# ElectronicThermometerCPO_v7.net
KiCad netlist of a schematic drawn in EAGLE
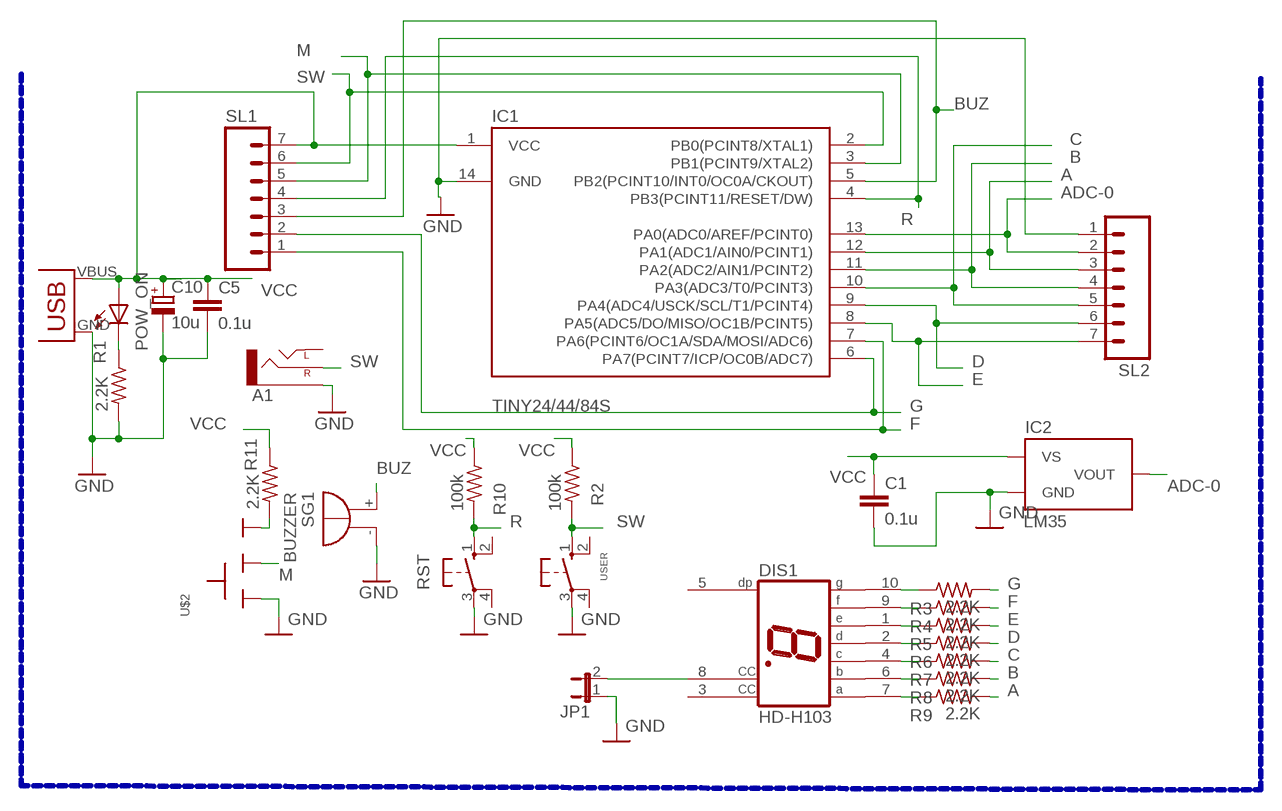
[diagram p0: schematic, sheet 1]

(export (version "E")
  (design (tool "Eeschema 10.0.6"))
  (components
    (comp (ref "A1")
      (value "AUDIO-JACKPTH")
      (footprint "eagle-import:AUDIO-JACK")
      (libsource (lib "eagle-import") (part "AUDIO-JACKPTH"))
    )
    (comp (ref "C1")
      (value "0.1u")
      (footprint "eagle-import:C0805")
      (libsource (lib "eagle-import") (part "C-EUC0805"))
    )
    (comp (ref "C5")
      (value "0.1u")
      (footprint "eagle-import:C0805")
      (libsource (lib "eagle-import") (part "C-EUC0805"))
    )
    (comp (ref "C10")
      (value "10u")
      (footprint "eagle-import:B_3528-21R")
      (libsource (lib "eagle-import") (part "CPOL-EUB/3528-21R"))
    )
    (comp (ref "DIS1")
      (value "HD-H103")
      (footprint "eagle-import:HDSP-M")
      (libsource (lib "eagle-import") (part "HD-H103"))
    )
    (comp (ref "IC1")
      (value "TINY24/44/84S")
      (footprint "eagle-import:SOIC14")
      (libsource (lib "eagle-import") (part "TINY24/44/84S"))
    )
    (comp (ref "IC2")
      (value "LM35")
      (footprint "eagle-import:TO92")
      (libsource (lib "eagle-import") (part "LM35"))
    )
    (comp (ref "JP1")
      (value "JP1E")
      (footprint "eagle-import:JP1")
      (libsource (lib "eagle-import") (part "JP1E"))
    )
    (comp (ref "POW_ON")
      (value "LED3MM")
      (footprint "eagle-import:LED3MM")
      (libsource (lib "eagle-import") (part "LED3MM"))
    )
    (comp (ref "R1")
      (value "2.2K")
      (footprint "eagle-import:0207_10")
      (libsource (lib "eagle-import") (part "R-US_0207/10"))
    )
    (comp (ref "R2")
      (value "100k")
      (footprint "eagle-import:0207_10")
      (libsource (lib "eagle-import") (part "R-US_0207/10"))
    )
    (comp (ref "R3")
      (value "2.2K")
      (footprint "eagle-import:0207_10")
      (libsource (lib "eagle-import") (part "R-US_0207/10"))
    )
    (comp (ref "R4")
      (value "2.2K")
      (footprint "eagle-import:0207_10")
      (libsource (lib "eagle-import") (part "R-US_0207/10"))
    )
    (comp (ref "R5")
      (value "2.2K")
      (footprint "eagle-import:0207_10")
      (libsource (lib "eagle-import") (part "R-US_0207/10"))
    )
    (comp (ref "R6")
      (value "2.2K")
      (footprint "eagle-import:0207_10")
      (libsource (lib "eagle-import") (part "R-US_0207/10"))
    )
    (comp (ref "R7")
      (value "2.2K")
      (footprint "eagle-import:0207_10")
      (libsource (lib "eagle-import") (part "R-US_0207/10"))
    )
    (comp (ref "R8")
      (value "2.2K")
      (footprint "eagle-import:0207_10")
      (libsource (lib "eagle-import") (part "R-US_0207/10"))
    )
    (comp (ref "R9")
      (value "2.2K")
      (footprint "eagle-import:0207_10")
      (libsource (lib "eagle-import") (part "R-US_0207/10"))
    )
    (comp (ref "R10")
      (value "100k")
      (footprint "eagle-import:0207_10")
      (libsource (lib "eagle-import") (part "R-US_0207/10"))
    )
    (comp (ref "R11")
      (value "2.2K")
      (footprint "eagle-import:0207_10")
      (libsource (lib "eagle-import") (part "R-US_0207/10"))
    )
    (comp (ref "RST")
      (value "10-XX")
      (footprint "eagle-import:B3F-10XX")
      (fields (field (name "MPN") "B3F-1000"))
      (libsource (lib "eagle-import") (part "10-XX"))
    )
    (comp (ref "SG1")
      (value "BUZZER")
      (footprint "eagle-import:F_TMB")
      (libsource (lib "eagle-import") (part "BUZZER"))
    )
    (comp (ref "SL1")
      (value "M07")
      (footprint "eagle-import:07P")
      (libsource (lib "eagle-import") (part "M07"))
    )
    (comp (ref "SL2")
      (value "M07")
      (footprint "eagle-import:07P")
      (libsource (lib "eagle-import") (part "M07"))
    )
    (comp (ref "U$1")
      (value "USB(POWER)")
      (footprint "eagle-import:USB(POWER)")
      (libsource (lib "eagle-import") (part "USB(POWER)"))
    )
    (comp (ref "U$2")
      (value "SLIDESWITCH-BIG")
      (footprint "eagle-import:BIGSWITCH")
      (libsource (lib "eagle-import") (part "SLIDESWITCH-BIG"))
    )
    (comp (ref "USER")
      (value "40-XX")
      (footprint "eagle-import:B3F-40XX")
      (fields (field (name "MF") "OMRON COMPONENTS USA") (field (name "MPN") "B3F-4000"))
      (libsource (lib "eagle-import") (part "40-XX"))
    )
  )
  (nets
    (net (code "1") (name "/A") (class "Default")
      (node (ref "IC1") (pin "12") (pinfunction "PA1(ADC1/AIN0/PCINT1)_12") (pintype "bidirectional"))
      (node (ref "R9") (pin "2") (pinfunction "2_2") (pintype "passive"))
      (node (ref "SL2") (pin "3") (pinfunction "3_3") (pintype "passive"))
    )
    (net (code "2") (name "/ADC-0") (class "Default")
      (node (ref "IC1") (pin "13") (pinfunction "PA0(ADC0/AREF/PCINT0)_13") (pintype "bidirectional"))
      (node (ref "IC2") (pin "VOUT") (pinfunction "VOUT_VOUT") (pintype "passive"))
      (node (ref "SL2") (pin "2") (pinfunction "2_2") (pintype "passive"))
    )
    (net (code "3") (name "/B") (class "Default")
      (node (ref "IC1") (pin "11") (pinfunction "PA2(ADC2/AIN1/PCINT2)_11") (pintype "bidirectional"))
      (node (ref "R8") (pin "2") (pinfunction "2_2") (pintype "passive"))
      (node (ref "SL2") (pin "4") (pinfunction "4_4") (pintype "passive"))
    )
    (net (code "4") (name "/BUZ") (class "Default")
      (node (ref "IC1") (pin "5") (pinfunction "PB2(PCINT10/INT0/OC0A/CKOUT)_5") (pintype "bidirectional"))
      (node (ref "SG1") (pin "+") (pinfunction "+_+") (pintype "passive"))
      (node (ref "SL1") (pin "3") (pinfunction "3_3") (pintype "passive"))
    )
    (net (code "5") (name "/C") (class "Default")
      (node (ref "IC1") (pin "10") (pinfunction "PA3(ADC3/T0/PCINT3)_10") (pintype "bidirectional"))
      (node (ref "R7") (pin "2") (pinfunction "2_2") (pintype "passive"))
      (node (ref "SL2") (pin "5") (pinfunction "5_5") (pintype "passive"))
    )
    (net (code "6") (name "/D") (class "Default")
      (node (ref "IC1") (pin "9") (pinfunction "PA4(ADC4/USCK/SCL/T1/PCINT4)_9") (pintype "bidirectional"))
      (node (ref "R6") (pin "2") (pinfunction "2_2") (pintype "passive"))
      (node (ref "SL2") (pin "6") (pinfunction "6_6") (pintype "passive"))
    )
    (net (code "7") (name "/E") (class "Default")
      (node (ref "IC1") (pin "8") (pinfunction "PA5(ADC5/DO/MISO/OC1B/PCINT5)_8") (pintype "bidirectional"))
      (node (ref "R5") (pin "2") (pinfunction "2_2") (pintype "passive"))
      (node (ref "SL2") (pin "7") (pinfunction "7_7") (pintype "passive"))
    )
    (net (code "8") (name "/F") (class "Default")
      (node (ref "IC1") (pin "7") (pinfunction "PA6(PCINT6/OC1A/SDA/MOSI/ADC6)_7") (pintype "bidirectional"))
      (node (ref "R4") (pin "2") (pinfunction "2_2") (pintype "passive"))
      (node (ref "SL1") (pin "1") (pinfunction "1_1") (pintype "passive"))
    )
    (net (code "9") (name "/G") (class "Default")
      (node (ref "IC1") (pin "6") (pinfunction "PA7(PCINT7/ICP/OC0B/ADC7)_6") (pintype "bidirectional"))
      (node (ref "R3") (pin "2") (pinfunction "2_2") (pintype "passive"))
      (node (ref "SL1") (pin "2") (pinfunction "2_2") (pintype "passive"))
    )
    (net (code "10") (name "/M") (class "Default")
      (node (ref "IC1") (pin "3") (pinfunction "PB1(PCINT9/XTAL2)_3") (pintype "bidirectional"))
      (node (ref "SL1") (pin "5") (pinfunction "5_5") (pintype "passive"))
      (node (ref "U$2") (pin "2") (pinfunction "2_2") (pintype "bidirectional"))
    )
    (net (code "11") (name "/R") (class "Default")
      (node (ref "IC1") (pin "4") (pinfunction "PB3(PCINT11/RESET/DW)_4") (pintype "bidirectional"))
      (node (ref "R10") (pin "2") (pinfunction "2_2") (pintype "passive"))
      (node (ref "RST") (pin "1") (pinfunction "S_1") (pintype "passive"))
      (node (ref "SL1") (pin "4") (pinfunction "4_4") (pintype "passive"))
    )
    (net (code "12") (name "/SW") (class "Default")
      (node (ref "A1") (pin "RING") (pinfunction "RIGHT_RING") (pintype "bidirectional"))
      (node (ref "IC1") (pin "2") (pinfunction "PB0(PCINT8/XTAL1)_2") (pintype "bidirectional"))
      (node (ref "R2") (pin "2") (pinfunction "2_2") (pintype "passive"))
      (node (ref "SL1") (pin "6") (pinfunction "6_6") (pintype "passive"))
      (node (ref "USER") (pin "1") (pinfunction "S_1") (pintype "passive"))
    )
    (net (code "13") (name "/VCC") (class "Default")
      (node (ref "C1") (pin "1") (pinfunction "1_1") (pintype "passive"))
      (node (ref "C10") (pin "+") (pinfunction "+_+") (pintype "passive"))
      (node (ref "C5") (pin "1") (pinfunction "1_1") (pintype "passive"))
      (node (ref "IC1") (pin "1") (pinfunction "VCC_1") (pintype "power_in"))
      (node (ref "IC2") (pin "VS") (pinfunction "VS_VS") (pintype "passive"))
      (node (ref "POW_ON") (pin "A") (pinfunction "A_A") (pintype "passive"))
      (node (ref "R10") (pin "1") (pinfunction "1_1") (pintype "passive"))
      (node (ref "R11") (pin "1") (pinfunction "1_1") (pintype "passive"))
      (node (ref "R2") (pin "1") (pinfunction "1_1") (pintype "passive"))
      (node (ref "SL1") (pin "7") (pinfunction "7_7") (pintype "passive"))
      (node (ref "U$1") (pin "VBUS") (pinfunction "VCC_VBUS") (pintype "power_in"))
    )
    (net (code "14") (name "GND") (class "Default")
      (node (ref "A1") (pin "SLEEVE") (pinfunction "SLEEVE_SLEEVE") (pintype "bidirectional"))
      (node (ref "C1") (pin "2") (pinfunction "2_2") (pintype "passive"))
      (node (ref "C10") (pin "-") (pinfunction "-_-") (pintype "passive"))
      (node (ref "C5") (pin "2") (pinfunction "2_2") (pintype "passive"))
      (node (ref "IC1") (pin "14") (pinfunction "GND_14") (pintype "power_in"))
      (node (ref "IC2") (pin "GND") (pinfunction "GND_GND") (pintype "passive"))
      (node (ref "JP1") (pin "1") (pinfunction "1_1") (pintype "passive"))
      (node (ref "R1") (pin "2") (pinfunction "2_2") (pintype "passive"))
      (node (ref "RST") (pin "3") (pinfunction "P_3") (pintype "passive"))
      (node (ref "SG1") (pin "-") (pinfunction "-_-") (pintype "passive"))
      (node (ref "SL2") (pin "1") (pinfunction "1_1") (pintype "passive"))
      (node (ref "U$1") (pin "GND") (pinfunction "GND_GND") (pintype "power_in"))
      (node (ref "U$2") (pin "1") (pinfunction "1_1") (pintype "bidirectional"))
      (node (ref "USER") (pin "3") (pinfunction "P_3") (pintype "passive"))
    )
    (net (code "15") (name "Net-(DIS1-A)") (class "Default")
      (node (ref "DIS1") (pin "7") (pinfunction "A_7") (pintype "passive"))
      (node (ref "R9") (pin "1") (pinfunction "1_1") (pintype "passive"))
    )
    (net (code "16") (name "Net-(DIS1-B)") (class "Default")
      (node (ref "DIS1") (pin "6") (pinfunction "B_6") (pintype "passive"))
      (node (ref "R8") (pin "1") (pinfunction "1_1") (pintype "passive"))
    )
    (net (code "17") (name "Net-(DIS1-C)") (class "Default")
      (node (ref "DIS1") (pin "4") (pinfunction "C_4") (pintype "passive"))
      (node (ref "R7") (pin "1") (pinfunction "1_1") (pintype "passive"))
    )
    (net (code "18") (name "Net-(DIS1-CC-Pad8)") (class "Default")
      (node (ref "DIS1") (pin "8") (pinfunction "CC_8") (pintype "passive"))
      (node (ref "JP1") (pin "2") (pinfunction "2_2") (pintype "passive"))
    )
    (net (code "19") (name "Net-(DIS1-D)") (class "Default")
      (node (ref "DIS1") (pin "2") (pinfunction "D_2") (pintype "passive"))
      (node (ref "R6") (pin "1") (pinfunction "1_1") (pintype "passive"))
    )
    (net (code "20") (name "Net-(DIS1-E)") (class "Default")
      (node (ref "DIS1") (pin "1") (pinfunction "E_1") (pintype "passive"))
      (node (ref "R5") (pin "1") (pinfunction "1_1") (pintype "passive"))
    )
    (net (code "21") (name "Net-(DIS1-F)") (class "Default")
      (node (ref "DIS1") (pin "9") (pinfunction "F_9") (pintype "passive"))
      (node (ref "R4") (pin "1") (pinfunction "1_1") (pintype "passive"))
    )
    (net (code "22") (name "Net-(DIS1-G)") (class "Default")
      (node (ref "DIS1") (pin "10") (pinfunction "G_10") (pintype "passive"))
      (node (ref "R3") (pin "1") (pinfunction "1_1") (pintype "passive"))
    )
    (net (code "23") (name "Net-(POW_ON-C)") (class "Default")
      (node (ref "POW_ON") (pin "K") (pinfunction "C_K") (pintype "passive"))
      (node (ref "R1") (pin "1") (pinfunction "1_1") (pintype "passive"))
    )
    (net (code "24") (name "Net-(R11-Pad2)") (class "Default")
      (node (ref "R11") (pin "2") (pinfunction "2_2") (pintype "passive"))
      (node (ref "U$2") (pin "3") (pinfunction "3_3") (pintype "bidirectional"))
    )
    (net (code "25") (name "unconnected-(A1-LEFT-PadTIP)") (class "Default")
      (node (ref "A1") (pin "TIP") (pinfunction "LEFT_TIP") (pintype "bidirectional"))
    )
    (net (code "26") (name "unconnected-(DIS1-CC-Pad3)") (class "Default")
      (node (ref "DIS1") (pin "3") (pinfunction "CC_3") (pintype "passive"))
    )
    (net (code "27") (name "unconnected-(DIS1-DP-Pad5)") (class "Default")
      (node (ref "DIS1") (pin "5") (pinfunction "DP_5") (pintype "passive"))
    )
    (net (code "28") (name "unconnected-(RST-P1-Pad4)") (class "Default")
      (node (ref "RST") (pin "4") (pinfunction "P1_4") (pintype "passive"))
    )
    (net (code "29") (name "unconnected-(RST-S1-Pad2)") (class "Default")
      (node (ref "RST") (pin "2") (pinfunction "S1_2") (pintype "passive"))
    )
    (net (code "30") (name "unconnected-(USER-P1-Pad4)") (class "Default")
      (node (ref "USER") (pin "4") (pinfunction "P1_4") (pintype "passive"))
    )
    (net (code "31") (name "unconnected-(USER-S1-Pad2)") (class "Default")
      (node (ref "USER") (pin "2") (pinfunction "S1_2") (pintype "passive"))
    )
  )
)
